# 5v-switch-sensor.net
KiCad netlist of a schematic drawn in EAGLE
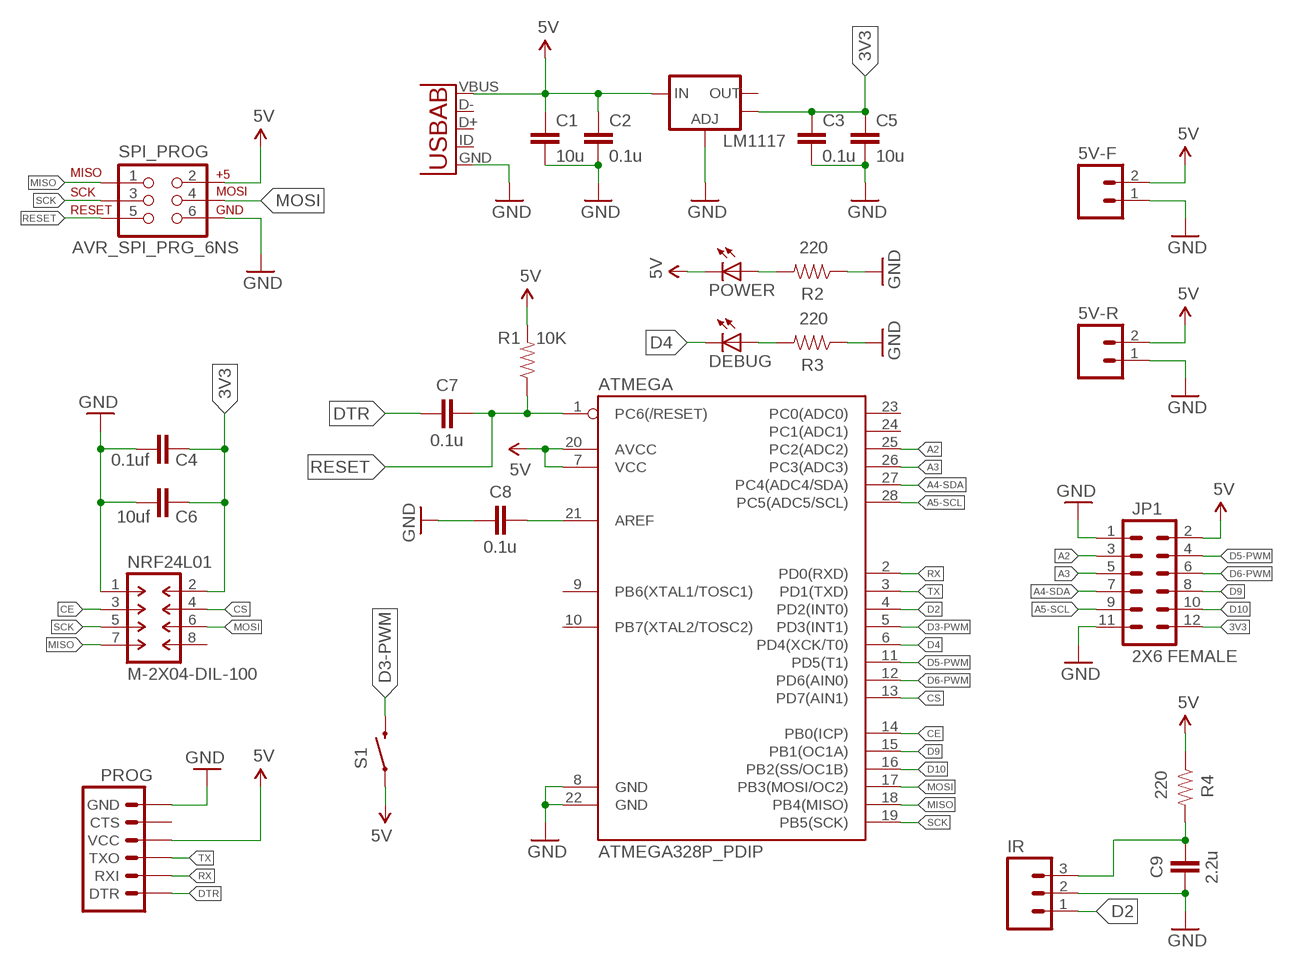
[diagram p0: schematic, sheet 1]

(export (version "E")
  (design (tool "Eeschema 10.0.6"))
  (components
    (comp (ref "5V-F")
      (value "M02PTH")
      (footprint "eagle-import:1X02")
      (libsource (lib "eagle-import") (part "M02PTH"))
    )
    (comp (ref "5V-R")
      (value "M02PTH")
      (footprint "eagle-import:1X02")
      (libsource (lib "eagle-import") (part "M02PTH"))
    )
    (comp (ref "ATMEGA")
      (value "ATMEGA328P_PDIP")
      (footprint "eagle-import:DIL28-3")
      (libsource (lib "eagle-import") (part "ATMEGA328P_PDIP"))
    )
    (comp (ref "C1")
      (value "10u")
      (footprint "eagle-import:0805")
      (libsource (lib "eagle-import") (part "CAP0805"))
    )
    (comp (ref "C2")
      (value "0.1u")
      (footprint "eagle-import:0805")
      (libsource (lib "eagle-import") (part "CAP0805"))
    )
    (comp (ref "C3")
      (value "0.1u")
      (footprint "eagle-import:0805")
      (libsource (lib "eagle-import") (part "CAP0805"))
    )
    (comp (ref "C4")
      (value "0.1uf")
      (footprint "eagle-import:0805")
      (libsource (lib "eagle-import") (part "CAP0805"))
    )
    (comp (ref "C5")
      (value "10u")
      (footprint "eagle-import:0805")
      (libsource (lib "eagle-import") (part "CAP0805"))
    )
    (comp (ref "C6")
      (value "10uf")
      (footprint "eagle-import:0805")
      (libsource (lib "eagle-import") (part "CAP0805"))
    )
    (comp (ref "C7")
      (value "0.1u")
      (footprint "eagle-import:0805")
      (libsource (lib "eagle-import") (part "CAP0805"))
    )
    (comp (ref "C8")
      (value "0.1u")
      (footprint "eagle-import:0805")
      (libsource (lib "eagle-import") (part "CAP0805"))
    )
    (comp (ref "C9")
      (value "2.2u")
      (footprint "eagle-import:0805")
      (libsource (lib "eagle-import") (part "CAP0805"))
    )
    (comp (ref "DEBUG")
      (value "LEDCHIPLED_0805")
      (footprint "eagle-import:CHIPLED_0805")
      (libsource (lib "eagle-import") (part "LEDCHIPLED_0805"))
    )
    (comp (ref "IR")
      (value "M03PTH")
      (footprint "eagle-import:1X03")
      (libsource (lib "eagle-import") (part "M03PTH"))
    )
    (comp (ref "JP1")
      (value "2X6 FEMALE")
      (footprint "eagle-import:2X6")
      (libsource (lib "eagle-import") (part "M06X2PTH_FEMALE"))
    )
    (comp (ref "LM1117")
      (value "V_REG_LM1117SOT223")
      (footprint "eagle-import:SOT223")
      (libsource (lib "eagle-import") (part "V_REG_LM1117SOT223"))
    )
    (comp (ref "NRF24L01")
      (value "M-2X04-DIL-100")
      (footprint "eagle-import:DIL-100-2X04")
      (libsource (lib "eagle-import") (part "M-2X04-DIL-100"))
    )
    (comp (ref "POWER")
      (value "LEDCHIPLED_0805")
      (footprint "eagle-import:CHIPLED_0805")
      (libsource (lib "eagle-import") (part "LEDCHIPLED_0805"))
    )
    (comp (ref "PROG")
      (value "ARDUINO_SERIAL_PROGRAMPTH")
      (footprint "eagle-import:1X06")
      (libsource (lib "eagle-import") (part "ARDUINO_SERIAL_PROGRAMPTH"))
    )
    (comp (ref "R1")
      (value "10K")
      (footprint "eagle-import:0805")
      (libsource (lib "eagle-import") (part "RESISTOR0805-RES"))
    )
    (comp (ref "R2")
      (value "220")
      (footprint "eagle-import:0805")
      (libsource (lib "eagle-import") (part "RESISTOR0805-RES"))
    )
    (comp (ref "R3")
      (value "220")
      (footprint "eagle-import:0805")
      (libsource (lib "eagle-import") (part "RESISTOR0805-RES"))
    )
    (comp (ref "R4")
      (value "220")
      (footprint "eagle-import:0805")
      (libsource (lib "eagle-import") (part "RESISTOR0805-RES"))
    )
    (comp (ref "S1")
      (value "SWITCH-MOMENTARY-2SMD-1101NE")
      (footprint "eagle-import:TACTILE-SWITCH-1101NE")
      (libsource (lib "eagle-import") (part "SWITCH-MOMENTARY-2SMD-1101NE"))
    )
    (comp (ref "SPI_PROG")
      (value "AVR_SPI_PRG_6NS")
      (footprint "eagle-import:2X3-NS")
      (libsource (lib "eagle-import") (part "AVR_SPI_PRG_6NS"))
    )
    (comp (ref "U1")
      (value "USB-AB")
      (footprint "eagle-import:USB-AB-MICRO-SMD")
      (libsource (lib "eagle-import") (part "USB-AB"))
    )
  )
  (nets
    (net (code "1") (name "3V3") (class "Default")
      (node (ref "C3") (pin "1") (pinfunction "1_1") (pintype "passive"))
      (node (ref "C4") (pin "1") (pinfunction "1_1") (pintype "passive"))
      (node (ref "C5") (pin "1") (pinfunction "1_1") (pintype "passive"))
      (node (ref "C6") (pin "1") (pinfunction "1_1") (pintype "passive"))
      (node (ref "JP1") (pin "12") (pinfunction "12_12") (pintype "passive"))
      (node (ref "LM1117") (pin "4") (pinfunction "OUT_4") (pintype "output"))
      (node (ref "NRF24L01") (pin "2") (pinfunction "2_2") (pintype "passive"))
    )
    (net (code "2") (name "5V") (class "Default")
      (node (ref "5V-F") (pin "2") (pinfunction "2_2") (pintype "passive"))
      (node (ref "5V-R") (pin "2") (pinfunction "2_2") (pintype "passive"))
      (node (ref "ATMEGA") (pin "20") (pinfunction "AVCC_20") (pintype "bidirectional"))
      (node (ref "ATMEGA") (pin "7") (pinfunction "VCC_7") (pintype "bidirectional"))
      (node (ref "C1") (pin "1") (pinfunction "1_1") (pintype "passive"))
      (node (ref "C2") (pin "1") (pinfunction "1_1") (pintype "passive"))
      (node (ref "JP1") (pin "2") (pinfunction "2_2") (pintype "passive"))
      (node (ref "LM1117") (pin "3") (pinfunction "IN_3") (pintype "input"))
      (node (ref "POWER") (pin "C") (pinfunction "C_C") (pintype "passive"))
      (node (ref "PROG") (pin "4") (pinfunction "VCC_4") (pintype "passive"))
      (node (ref "R1") (pin "2") (pinfunction "2_2") (pintype "passive"))
      (node (ref "R4") (pin "1") (pinfunction "1_1") (pintype "passive"))
      (node (ref "S1") (pin "1") (pinfunction "1_1") (pintype "passive"))
      (node (ref "SPI_PROG") (pin "2") (pinfunction "2_2") (pintype "passive"))
      (node (ref "U1") (pin "VBUS") (pinfunction "VBUS_VBUS") (pintype "bidirectional"))
    )
    (net (code "3") (name "A2") (class "Default")
      (node (ref "ATMEGA") (pin "25") (pinfunction "PC2(ADC2)_25") (pintype "bidirectional"))
      (node (ref "JP1") (pin "3") (pinfunction "3_3") (pintype "passive"))
    )
    (net (code "4") (name "A3") (class "Default")
      (node (ref "ATMEGA") (pin "26") (pinfunction "PC3(ADC3)_26") (pintype "bidirectional"))
      (node (ref "JP1") (pin "5") (pinfunction "5_5") (pintype "passive"))
    )
    (net (code "5") (name "A4-SDA") (class "Default")
      (node (ref "ATMEGA") (pin "27") (pinfunction "PC4(ADC4/SDA)_27") (pintype "bidirectional"))
      (node (ref "JP1") (pin "7") (pinfunction "7_7") (pintype "passive"))
    )
    (net (code "6") (name "A5-SCL") (class "Default")
      (node (ref "ATMEGA") (pin "28") (pinfunction "PC5(ADC5/SCL)_28") (pintype "bidirectional"))
      (node (ref "JP1") (pin "9") (pinfunction "9_9") (pintype "passive"))
    )
    (net (code "7") (name "CE") (class "Default")
      (node (ref "ATMEGA") (pin "14") (pinfunction "PB0(ICP)_14") (pintype "bidirectional"))
      (node (ref "NRF24L01") (pin "3") (pinfunction "3_3") (pintype "passive"))
    )
    (net (code "8") (name "CS") (class "Default")
      (node (ref "ATMEGA") (pin "13") (pinfunction "PD7(AIN1)_13") (pintype "bidirectional"))
      (node (ref "NRF24L01") (pin "4") (pinfunction "4_4") (pintype "passive"))
    )
    (net (code "9") (name "D2") (class "Default")
      (node (ref "ATMEGA") (pin "4") (pinfunction "PD2(INT0)_4") (pintype "bidirectional"))
      (node (ref "IR") (pin "1") (pinfunction "1_1") (pintype "passive"))
    )
    (net (code "10") (name "D3-PWM") (class "Default")
      (node (ref "ATMEGA") (pin "5") (pinfunction "PD3(INT1)_5") (pintype "bidirectional"))
      (node (ref "S1") (pin "2") (pinfunction "2_2") (pintype "passive"))
    )
    (net (code "11") (name "D4") (class "Default")
      (node (ref "ATMEGA") (pin "6") (pinfunction "PD4(XCK/T0)_6") (pintype "bidirectional"))
      (node (ref "DEBUG") (pin "C") (pinfunction "C_C") (pintype "passive"))
    )
    (net (code "12") (name "D5-PWM") (class "Default")
      (node (ref "ATMEGA") (pin "11") (pinfunction "PD5(T1)_11") (pintype "bidirectional"))
      (node (ref "JP1") (pin "4") (pinfunction "4_4") (pintype "passive"))
    )
    (net (code "13") (name "D6-PWM") (class "Default")
      (node (ref "ATMEGA") (pin "12") (pinfunction "PD6(AIN0)_12") (pintype "bidirectional"))
      (node (ref "JP1") (pin "6") (pinfunction "6_6") (pintype "passive"))
    )
    (net (code "14") (name "D9") (class "Default")
      (node (ref "ATMEGA") (pin "15") (pinfunction "PB1(OC1A)_15") (pintype "bidirectional"))
      (node (ref "JP1") (pin "8") (pinfunction "8_8") (pintype "passive"))
    )
    (net (code "15") (name "D10") (class "Default")
      (node (ref "ATMEGA") (pin "16") (pinfunction "PB2(SS/OC1B)_16") (pintype "bidirectional"))
      (node (ref "JP1") (pin "10") (pinfunction "10_10") (pintype "passive"))
    )
    (net (code "16") (name "DTR") (class "Default")
      (node (ref "C7") (pin "1") (pinfunction "1_1") (pintype "passive"))
      (node (ref "PROG") (pin "1") (pinfunction "DTR_1") (pintype "passive"))
    )
    (net (code "17") (name "GND") (class "Default")
      (node (ref "5V-F") (pin "1") (pinfunction "1_1") (pintype "passive"))
      (node (ref "5V-R") (pin "1") (pinfunction "1_1") (pintype "passive"))
      (node (ref "ATMEGA") (pin "22") (pinfunction "GND_22") (pintype "bidirectional"))
      (node (ref "ATMEGA") (pin "8") (pinfunction "GND_8") (pintype "bidirectional"))
      (node (ref "C1") (pin "2") (pinfunction "2_2") (pintype "passive"))
      (node (ref "C2") (pin "2") (pinfunction "2_2") (pintype "passive"))
      (node (ref "C3") (pin "2") (pinfunction "2_2") (pintype "passive"))
      (node (ref "C4") (pin "2") (pinfunction "2_2") (pintype "passive"))
      (node (ref "C5") (pin "2") (pinfunction "2_2") (pintype "passive"))
      (node (ref "C6") (pin "2") (pinfunction "2_2") (pintype "passive"))
      (node (ref "C8") (pin "1") (pinfunction "1_1") (pintype "passive"))
      (node (ref "C9") (pin "1") (pinfunction "1_1") (pintype "passive"))
      (node (ref "IR") (pin "2") (pinfunction "2_2") (pintype "passive"))
      (node (ref "JP1") (pin "1") (pinfunction "1_1") (pintype "passive"))
      (node (ref "JP1") (pin "11") (pinfunction "11_11") (pintype "passive"))
      (node (ref "LM1117") (pin "1") (pinfunction "ADJ_1") (pintype "input"))
      (node (ref "NRF24L01") (pin "1") (pinfunction "1_1") (pintype "passive"))
      (node (ref "PROG") (pin "6") (pinfunction "GND_6") (pintype "passive"))
      (node (ref "R2") (pin "1") (pinfunction "1_1") (pintype "passive"))
      (node (ref "R3") (pin "1") (pinfunction "1_1") (pintype "passive"))
      (node (ref "SPI_PROG") (pin "6") (pinfunction "6_6") (pintype "passive"))
      (node (ref "U1") (pin "GND") (pinfunction "GND_GND") (pintype "bidirectional"))
    )
    (net (code "18") (name "MISO") (class "Default")
      (node (ref "ATMEGA") (pin "18") (pinfunction "PB4(MISO)_18") (pintype "bidirectional"))
      (node (ref "NRF24L01") (pin "7") (pinfunction "7_7") (pintype "passive"))
      (node (ref "SPI_PROG") (pin "1") (pinfunction "1_1") (pintype "passive"))
    )
    (net (code "19") (name "MOSI") (class "Default")
      (node (ref "ATMEGA") (pin "17") (pinfunction "PB3(MOSI/OC2)_17") (pintype "bidirectional"))
      (node (ref "NRF24L01") (pin "6") (pinfunction "6_6") (pintype "passive"))
      (node (ref "SPI_PROG") (pin "4") (pinfunction "4_4") (pintype "passive"))
    )
    (net (code "20") (name "Net-(ATMEGA-AREF)") (class "Default")
      (node (ref "ATMEGA") (pin "21") (pinfunction "AREF_21") (pintype "bidirectional"))
      (node (ref "C8") (pin "2") (pinfunction "2_2") (pintype "passive"))
    )
    (net (code "21") (name "Net-(C9-Pad2)") (class "Default")
      (node (ref "C9") (pin "2") (pinfunction "2_2") (pintype "passive"))
      (node (ref "IR") (pin "3") (pinfunction "3_3") (pintype "passive"))
      (node (ref "R4") (pin "2") (pinfunction "2_2") (pintype "passive"))
    )
    (net (code "22") (name "Net-(DEBUG-PadA)") (class "Default")
      (node (ref "DEBUG") (pin "A") (pinfunction "A_A") (pintype "passive"))
      (node (ref "R3") (pin "2") (pinfunction "2_2") (pintype "passive"))
    )
    (net (code "23") (name "Net-(POWER-PadA)") (class "Default")
      (node (ref "POWER") (pin "A") (pinfunction "A_A") (pintype "passive"))
      (node (ref "R2") (pin "2") (pinfunction "2_2") (pintype "passive"))
    )
    (net (code "24") (name "RESET") (class "Default")
      (node (ref "ATMEGA") (pin "1") (pinfunction "PC6(/RESET)_1") (pintype "bidirectional"))
      (node (ref "C7") (pin "2") (pinfunction "2_2") (pintype "passive"))
      (node (ref "R1") (pin "1") (pinfunction "1_1") (pintype "passive"))
      (node (ref "SPI_PROG") (pin "5") (pinfunction "5_5") (pintype "passive"))
    )
    (net (code "25") (name "RX") (class "Default")
      (node (ref "ATMEGA") (pin "2") (pinfunction "PD0(RXD)_2") (pintype "bidirectional"))
      (node (ref "PROG") (pin "2") (pinfunction "RXI_2") (pintype "passive"))
    )
    (net (code "26") (name "SCK") (class "Default")
      (node (ref "ATMEGA") (pin "19") (pinfunction "PB5(SCK)_19") (pintype "bidirectional"))
      (node (ref "NRF24L01") (pin "5") (pinfunction "5_5") (pintype "passive"))
      (node (ref "SPI_PROG") (pin "3") (pinfunction "3_3") (pintype "passive"))
    )
    (net (code "27") (name "TX") (class "Default")
      (node (ref "ATMEGA") (pin "3") (pinfunction "PD1(TXD)_3") (pintype "bidirectional"))
      (node (ref "PROG") (pin "3") (pinfunction "TXO_3") (pintype "passive"))
    )
    (net (code "28") (name "unconnected-(ATMEGA-PB6(XTAL1{slash}TOSC1)-Pad9)") (class "Default")
      (node (ref "ATMEGA") (pin "9") (pinfunction "PB6(XTAL1/TOSC1)_9") (pintype "bidirectional"))
    )
    (net (code "29") (name "unconnected-(ATMEGA-PB7(XTAL2{slash}TOSC2)-Pad10)") (class "Default")
      (node (ref "ATMEGA") (pin "10") (pinfunction "PB7(XTAL2/TOSC2)_10") (pintype "bidirectional"))
    )
    (net (code "30") (name "unconnected-(ATMEGA-PC0(ADC0)-Pad23)") (class "Default")
      (node (ref "ATMEGA") (pin "23") (pinfunction "PC0(ADC0)_23") (pintype "bidirectional"))
    )
    (net (code "31") (name "unconnected-(ATMEGA-PC1(ADC1)-Pad24)") (class "Default")
      (node (ref "ATMEGA") (pin "24") (pinfunction "PC1(ADC1)_24") (pintype "bidirectional"))
    )
    (net (code "32") (name "unconnected-(LM1117-OUT-Pad2)") (class "Default")
      (node (ref "LM1117") (pin "2") (pinfunction "OUT_2") (pintype "output"))
    )
    (net (code "33") (name "unconnected-(NRF24L01-Pad8)") (class "Default")
      (node (ref "NRF24L01") (pin "8") (pinfunction "8_8") (pintype "passive"))
    )
    (net (code "34") (name "unconnected-(PROG-CTS-Pad5)") (class "Default")
      (node (ref "PROG") (pin "5") (pinfunction "CTS_5") (pintype "passive"))
    )
    (net (code "35") (name "unconnected-(U1-PadD+)") (class "Default")
      (node (ref "U1") (pin "D+") (pinfunction "D+_D+") (pintype "bidirectional"))
    )
    (net (code "36") (name "unconnected-(U1-PadD-)") (class "Default")
      (node (ref "U1") (pin "D-") (pinfunction "D-_D-") (pintype "bidirectional"))
    )
    (net (code "37") (name "unconnected-(U1-USBID-PadID)") (class "Default")
      (node (ref "U1") (pin "ID") (pinfunction "USBID_ID") (pintype "bidirectional"))
    )
  )
)
